# 04_LORA.net
KiCad netlist of a schematic drawn in Altium Designer
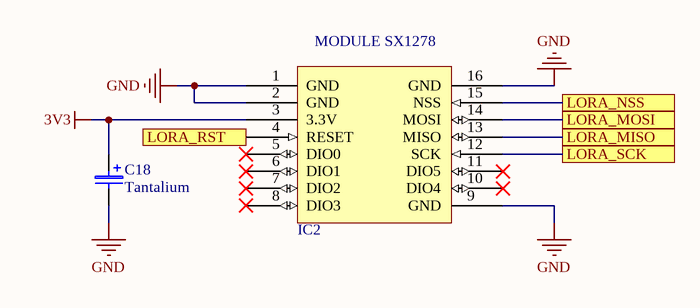
[diagram p0: [04].LORA.SchDoc]

(export (version "E")
  (design (tool "Eeschema 10.0.6"))
  (components
    (comp (ref "C18") (value "Tantalium") (footprint "Case A") (libsource (lib "MDBK") (part "CASE A")))
    (comp (ref "IC2")
      (value "MODULE SX1278")
      (footprint "LORA_RA01")
      (description "IC RF TXRX 802.15.4 28VQFN")
      (fields
        (field (name "PART NUMBER") "SX1278IMLTRT")
        (field (name "DEVICE") "MODULE SX1278")
        (field (name "MANUFACTURER") "Semtech Corporation")
        (field (name "AUTHOR") "MDBK")
      )
      (libsource (lib "ICs And Semiconductors") (part "MODULE LORA"))
    )
  )
  (nets
    (net (code "1") (name "/LORA_MISO") (class "Default")
      (node (ref "IC2") (pin "13") (pinfunction "MISO_13") (pintype "bidirectional"))
    )
    (net (code "2") (name "/LORA_MOSI") (class "Default")
      (node (ref "IC2") (pin "14") (pinfunction "MOSI_14") (pintype "bidirectional"))
    )
    (net (code "3") (name "/LORA_NSS") (class "Default")
      (node (ref "IC2") (pin "15") (pinfunction "NSS_15") (pintype "input"))
    )
    (net (code "4") (name "/LORA_RST") (class "Default")
      (node (ref "IC2") (pin "4") (pinfunction "RESET_4") (pintype "input"))
    )
    (net (code "5") (name "/LORA_SCK") (class "Default")
      (node (ref "IC2") (pin "12") (pinfunction "SCK_12") (pintype "input"))
    )
    (net (code "6") (name "3V3") (class "Default")
      (node (ref "C18") (pin "A") (pinfunction "A_A") (pintype "passive"))
      (node (ref "IC2") (pin "3") (pinfunction "3.3V_3") (pintype "power_in"))
    )
    (net (code "7") (name "GND") (class "Default")
      (node (ref "C18") (pin "K") (pinfunction "K_K") (pintype "passive"))
      (node (ref "IC2") (pin "1") (pinfunction "GND_1") (pintype "passive"))
      (node (ref "IC2") (pin "16") (pinfunction "GND_16") (pintype "power_in"))
      (node (ref "IC2") (pin "2") (pinfunction "GND_2") (pintype "power_in"))
      (node (ref "IC2") (pin "9") (pinfunction "GND_9") (pintype "power_in"))
    )
    (net (code "8") (name "unconnected-(IC2-DIO0-Pad5)") (class "Default")
      (node (ref "IC2") (pin "5") (pinfunction "DIO0_5") (pintype "bidirectional+no_connect"))
    )
    (net (code "9") (name "unconnected-(IC2-DIO1-Pad6)") (class "Default")
      (node (ref "IC2") (pin "6") (pinfunction "DIO1_6") (pintype "bidirectional+no_connect"))
    )
    (net (code "10") (name "unconnected-(IC2-DIO2-Pad7)") (class "Default")
      (node (ref "IC2") (pin "7") (pinfunction "DIO2_7") (pintype "bidirectional+no_connect"))
    )
    (net (code "11") (name "unconnected-(IC2-DIO3-Pad8)") (class "Default")
      (node (ref "IC2") (pin "8") (pinfunction "DIO3_8") (pintype "bidirectional+no_connect"))
    )
    (net (code "12") (name "unconnected-(IC2-DIO4-Pad10)") (class "Default")
      (node (ref "IC2") (pin "10") (pinfunction "DIO4_10") (pintype "bidirectional+no_connect"))
    )
    (net (code "13") (name "unconnected-(IC2-DIO5-Pad11)") (class "Default")
      (node (ref "IC2") (pin "11") (pinfunction "DIO5_11") (pintype "bidirectional+no_connect"))
    )
  )
)
